# Schmatics_Hist_Prep.net
KiCad netlist of a schematic drawn in Altium Designer
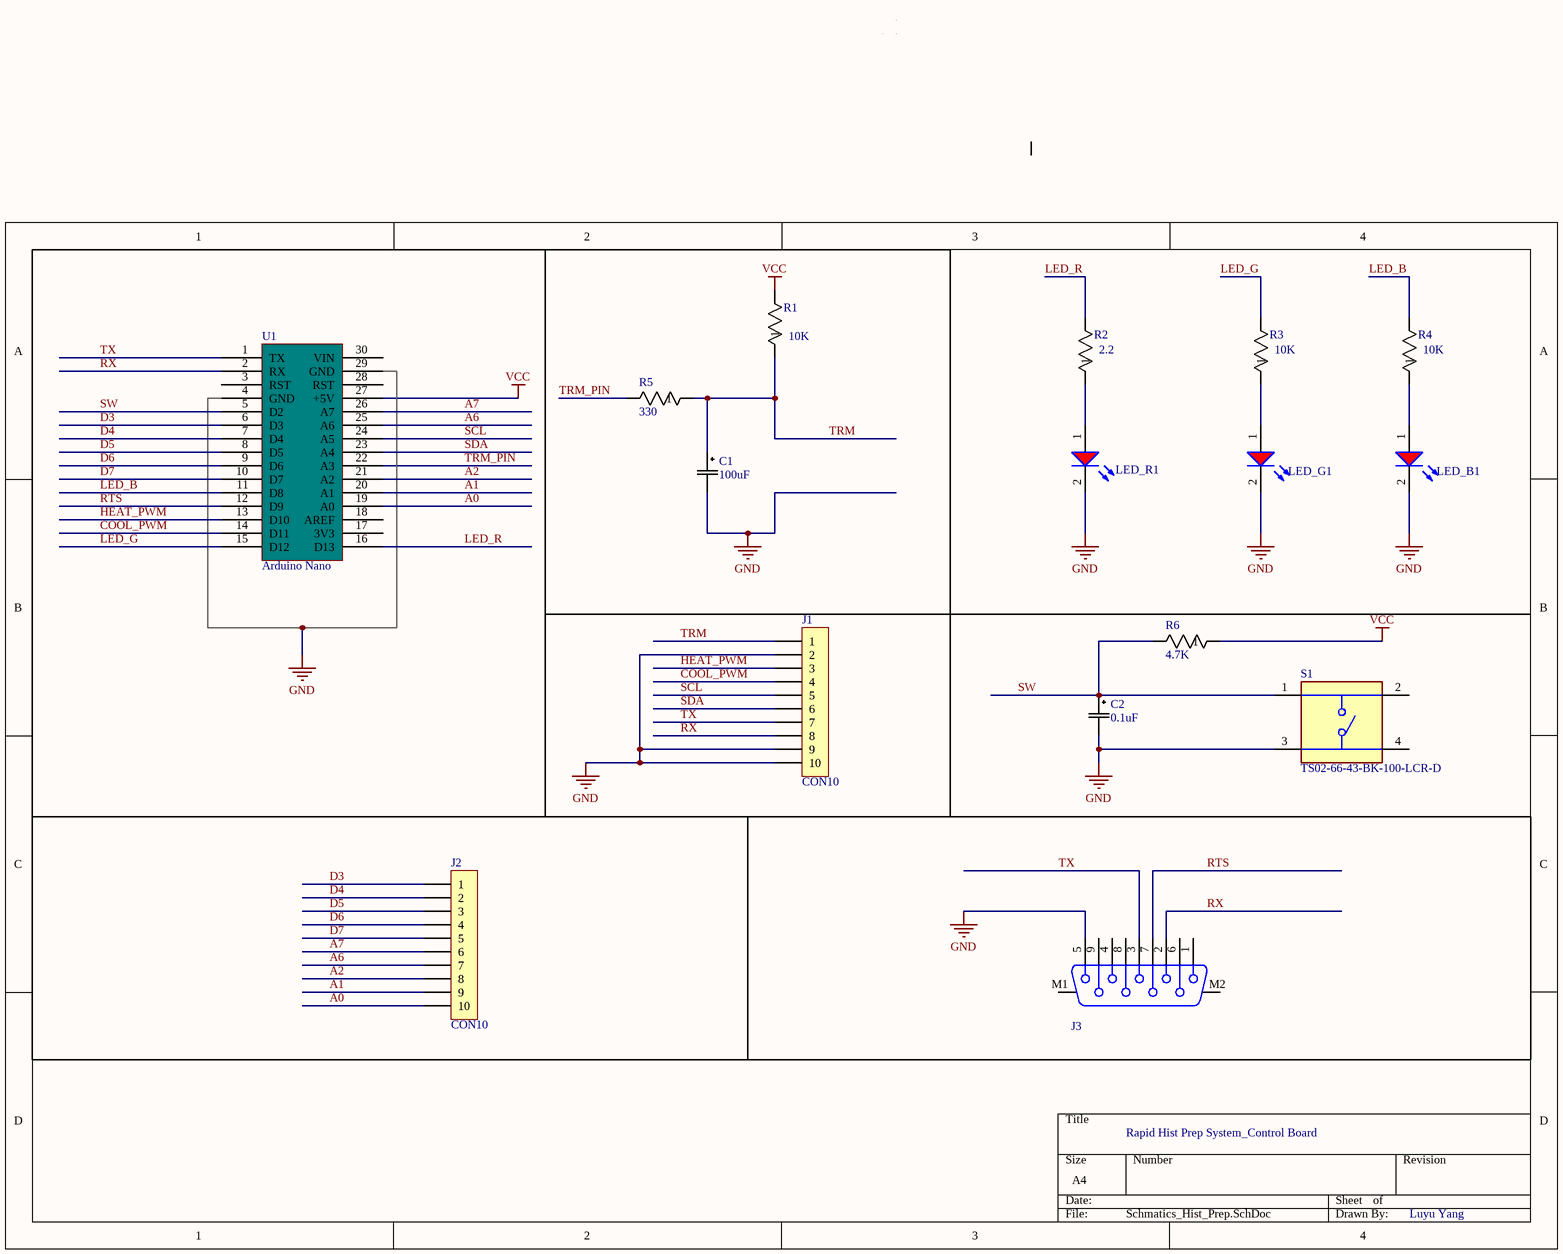
[diagram p0: Schmatics_Hist_Prep.SchDoc]

(export (version "E")
  (design (tool "Eeschema 10.0.6"))
  (components
    (comp (ref "C1")
      (value "100uF")
      (footprint "CAP_UKL_5X11_NCH")
      (description "No Description Available")
      (libsource (lib "UKL1H0R1MDDANATA") (part "UKL1H0R1MDDANATA"))
    )
    (comp (ref "C2")
      (value "0.1uF")
      (footprint "CAP_UKL_5X11_NCH")
      (description "No Description Available")
      (libsource (lib "UKL1H0R1MDDANATA") (part "UKL1H0R1MDDANATA"))
    )
    (comp (ref "J1") (value "CON10") (footprint "sip10") (libsource (lib "常用元件库") (part "CON10")))
    (comp (ref "J2") (value "CON10") (footprint "sip10") (libsource (lib "常用元件库") (part "CON10")))
    (comp (ref "J3")
      (value "61800925123")
      (footprint "61800925123")
      (description "WR-DSUB Female PCB Connector, Straight, 9p")
      (fields (field (name "MANUFACTURER") "Wurth Elektronik"))
      (libsource (lib "WR-DSUB") (part "61800925123"))
    )
    (comp (ref "LED_B1")
      (value "Super Red, 2V, 40°")
      (footprint "WL-TMRC_D3.95H5.3")
      (description "WL-TMRC Mono-color Round Color, THT, D3.95 x H5.3mm, Super Red, 2V, 40°")
      (fields
        (field (name "MANUFACTURER PART NUMBER") "151031SS04000")
        (field (name "MANUFACTURER") "Wurth Elektronik")
      )
      (libsource (lib "Altium_WL-TMRC_rev22b") (part "151031SS04000"))
    )
    (comp (ref "LED_G1")
      (value "Super Red, 2V, 40°")
      (footprint "WL-TMRC_D3.95H5.3")
      (description "WL-TMRC Mono-color Round Color, THT, D3.95 x H5.3mm, Super Red, 2V, 40°")
      (fields
        (field (name "MANUFACTURER PART NUMBER") "151031SS04000")
        (field (name "MANUFACTURER") "Wurth Elektronik")
      )
      (libsource (lib "Altium_WL-TMRC_rev22b") (part "151031SS04000"))
    )
    (comp (ref "LED_R1")
      (value "Super Red, 2V, 40°")
      (footprint "WL-TMRC_D3.95H5.3")
      (description "WL-TMRC Mono-color Round Color, THT, D3.95 x H5.3mm, Super Red, 2V, 40°")
      (fields
        (field (name "MANUFACTURER PART NUMBER") "151031SS04000")
        (field (name "MANUFACTURER") "Wurth Elektronik")
      )
      (libsource (lib "Altium_WL-TMRC_rev22b") (part "151031SS04000"))
    )
    (comp (ref "R1")
      (value "10K")
      (footprint "STA_CF14_STP")
      (description "No Description Available")
      (libsource (lib "CF14JT1K00") (part "CF14JT1K00"))
    )
    (comp (ref "R2")
      (value "2.2")
      (footprint "STA_CF14_STP")
      (description "No Description Available")
      (libsource (lib "CF14JT1K00") (part "CF14JT1K00"))
    )
    (comp (ref "R3")
      (value "10K")
      (footprint "STA_CF14_STP")
      (description "No Description Available")
      (libsource (lib "CF14JT1K00") (part "CF14JT1K00"))
    )
    (comp (ref "R4")
      (value "10K")
      (footprint "STA_CF14_STP")
      (description "No Description Available")
      (libsource (lib "CF14JT1K00") (part "CF14JT1K00"))
    )
    (comp (ref "R5")
      (value "330")
      (footprint "STA_CF14_STP")
      (description "No Description Available")
      (libsource (lib "CF14JT1K00") (part "CF14JT1K00"))
    )
    (comp (ref "R6")
      (value "4.7K")
      (footprint "STA_CF14_STP")
      (description "No Description Available")
      (libsource (lib "CF14JT1K00") (part "CF14JT1K00"))
    )
    (comp (ref "S1")
      (value "TS02-66-43-BK-100-LCR-D")
      (footprint "SW_TS02-66-43-BK-100-LCR-D")
      (description "6 x 6 mm, 4.3 mm Actuator Height, 100 gf, Black, Long Crimped, Through Hole, SPST, Tactile Switch")
      (fields (field (name "MF") "CUI Devices"))
      (libsource (lib "TS02-66-43-BK-100-LCR-D") (part "TS02-66-43-BK-100-LCR-D"))
    )
    (comp (ref "U1")
      (value "Arduino Nano")
      (footprint "PCBComponent_1")
      (libsource (lib "Nano") (part "Component_1"))
    )
  )
  (nets
    (net (code "1") (name "/A0") (class "Default")
      (node (ref "J2") (pin "10") (pinfunction "10_10") (pintype "passive"))
      (node (ref "U1") (pin "19") (pinfunction "A0_19") (pintype "passive"))
    )
    (net (code "2") (name "/A1") (class "Default")
      (node (ref "J2") (pin "9") (pinfunction "9_9") (pintype "passive"))
      (node (ref "U1") (pin "20") (pinfunction "A1_20") (pintype "passive"))
    )
    (net (code "3") (name "/A2") (class "Default")
      (node (ref "J2") (pin "8") (pinfunction "8_8") (pintype "passive"))
      (node (ref "U1") (pin "21") (pinfunction "A2_21") (pintype "passive"))
    )
    (net (code "4") (name "/A6") (class "Default")
      (node (ref "J2") (pin "7") (pinfunction "7_7") (pintype "passive"))
      (node (ref "U1") (pin "25") (pinfunction "A6_25") (pintype "passive"))
    )
    (net (code "5") (name "/A7") (class "Default")
      (node (ref "J2") (pin "6") (pinfunction "6_6") (pintype "passive"))
      (node (ref "U1") (pin "26") (pinfunction "A7_26") (pintype "passive"))
    )
    (net (code "6") (name "/COOL_PWM") (class "Default")
      (node (ref "J1") (pin "4") (pinfunction "4_4") (pintype "passive"))
      (node (ref "U1") (pin "14") (pinfunction "D11_14") (pintype "passive"))
    )
    (net (code "7") (name "/D3") (class "Default")
      (node (ref "J2") (pin "1") (pinfunction "1_1") (pintype "passive"))
      (node (ref "U1") (pin "6") (pinfunction "D3_6") (pintype "passive"))
    )
    (net (code "8") (name "/D4") (class "Default")
      (node (ref "J2") (pin "2") (pinfunction "2_2") (pintype "passive"))
      (node (ref "U1") (pin "7") (pinfunction "D4_7") (pintype "passive"))
    )
    (net (code "9") (name "/D5") (class "Default")
      (node (ref "J2") (pin "3") (pinfunction "3_3") (pintype "passive"))
      (node (ref "U1") (pin "8") (pinfunction "D5_8") (pintype "passive"))
    )
    (net (code "10") (name "/D6") (class "Default")
      (node (ref "J2") (pin "4") (pinfunction "4_4") (pintype "passive"))
      (node (ref "U1") (pin "9") (pinfunction "D6_9") (pintype "passive"))
    )
    (net (code "11") (name "/D7") (class "Default")
      (node (ref "J2") (pin "5") (pinfunction "5_5") (pintype "passive"))
      (node (ref "U1") (pin "10") (pinfunction "D7_10") (pintype "passive"))
    )
    (net (code "12") (name "/HEAT_PWM") (class "Default")
      (node (ref "J1") (pin "3") (pinfunction "3_3") (pintype "passive"))
      (node (ref "U1") (pin "13") (pinfunction "D10_13") (pintype "passive"))
    )
    (net (code "13") (name "/LED_B") (class "Default")
      (node (ref "R4") (pin "2") (pinfunction "2_2") (pintype "passive"))
      (node (ref "U1") (pin "11") (pinfunction "D8_11") (pintype "passive"))
    )
    (net (code "14") (name "/LED_G") (class "Default")
      (node (ref "R3") (pin "2") (pinfunction "2_2") (pintype "passive"))
      (node (ref "U1") (pin "15") (pinfunction "D12_15") (pintype "passive"))
    )
    (net (code "15") (name "/LED_R") (class "Default")
      (node (ref "R2") (pin "2") (pinfunction "2_2") (pintype "passive"))
      (node (ref "U1") (pin "16") (pinfunction "D13_16") (pintype "passive"))
    )
    (net (code "16") (name "/RTS") (class "Default")
      (node (ref "J3") (pin "7") (pinfunction "7_7") (pintype "passive"))
      (node (ref "U1") (pin "12") (pinfunction "D9_12") (pintype "passive"))
    )
    (net (code "17") (name "/RX") (class "Default")
      (node (ref "J1") (pin "8") (pinfunction "8_8") (pintype "passive"))
      (node (ref "J3") (pin "2") (pinfunction "2_2") (pintype "passive"))
      (node (ref "U1") (pin "2") (pinfunction "RX_2") (pintype "passive"))
    )
    (net (code "18") (name "/SCL") (class "Default")
      (node (ref "J1") (pin "5") (pinfunction "5_5") (pintype "passive"))
      (node (ref "U1") (pin "24") (pinfunction "A5_24") (pintype "passive"))
    )
    (net (code "19") (name "/SDA") (class "Default")
      (node (ref "J1") (pin "6") (pinfunction "6_6") (pintype "passive"))
      (node (ref "U1") (pin "23") (pinfunction "A4_23") (pintype "passive"))
    )
    (net (code "20") (name "/SW") (class "Default")
      (node (ref "C2") (pin "1") (pinfunction "1_1") (pintype "passive"))
      (node (ref "R6") (pin "2") (pinfunction "2_2") (pintype "passive"))
      (node (ref "S1") (pin "1") (pinfunction "1_1") (pintype "passive"))
      (node (ref "U1") (pin "5") (pinfunction "D2_5") (pintype "passive"))
    )
    (net (code "21") (name "/TRM") (class "Default")
      (node (ref "C1") (pin "1") (pinfunction "1_1") (pintype "passive"))
      (node (ref "J1") (pin "1") (pinfunction "1_1") (pintype "passive"))
      (node (ref "R1") (pin "1") (pinfunction "1_1") (pintype "passive"))
      (node (ref "R5") (pin "1") (pinfunction "1_1") (pintype "passive"))
    )
    (net (code "22") (name "/TRM_PIN") (class "Default")
      (node (ref "R5") (pin "2") (pinfunction "2_2") (pintype "passive"))
      (node (ref "U1") (pin "22") (pinfunction "A3_22") (pintype "passive"))
    )
    (net (code "23") (name "/TX") (class "Default")
      (node (ref "J1") (pin "7") (pinfunction "7_7") (pintype "passive"))
      (node (ref "J3") (pin "3") (pinfunction "3_3") (pintype "passive"))
      (node (ref "U1") (pin "1") (pinfunction "TX_1") (pintype "passive"))
    )
    (net (code "24") (name "GND") (class "Default")
      (node (ref "C1") (pin "2") (pinfunction "2_2") (pintype "passive"))
      (node (ref "C2") (pin "2") (pinfunction "2_2") (pintype "passive"))
      (node (ref "J1") (pin "10") (pinfunction "10_10") (pintype "passive"))
      (node (ref "J1") (pin "2") (pinfunction "2_2") (pintype "passive"))
      (node (ref "J1") (pin "9") (pinfunction "9_9") (pintype "passive"))
      (node (ref "J3") (pin "5") (pinfunction "5_5") (pintype "passive"))
      (node (ref "LED_B1") (pin "2") (pinfunction "K_2") (pintype "passive"))
      (node (ref "LED_G1") (pin "2") (pinfunction "K_2") (pintype "passive"))
      (node (ref "LED_R1") (pin "2") (pinfunction "K_2") (pintype "passive"))
      (node (ref "S1") (pin "3") (pinfunction "3_3") (pintype "passive"))
      (node (ref "U1") (pin "29") (pinfunction "GND_29") (pintype "passive"))
      (node (ref "U1") (pin "4") (pinfunction "GND_4") (pintype "passive"))
    )
    (net (code "25") (name "Net-(LED_B1-A)") (class "Default")
      (node (ref "LED_B1") (pin "1") (pinfunction "A_1") (pintype "passive"))
      (node (ref "R4") (pin "1") (pinfunction "1_1") (pintype "passive"))
    )
    (net (code "26") (name "Net-(LED_G1-A)") (class "Default")
      (node (ref "LED_G1") (pin "1") (pinfunction "A_1") (pintype "passive"))
      (node (ref "R3") (pin "1") (pinfunction "1_1") (pintype "passive"))
    )
    (net (code "27") (name "Net-(LED_R1-A)") (class "Default")
      (node (ref "LED_R1") (pin "1") (pinfunction "A_1") (pintype "passive"))
      (node (ref "R2") (pin "1") (pinfunction "1_1") (pintype "passive"))
    )
    (net (code "28") (name "VCC") (class "Default")
      (node (ref "R1") (pin "2") (pinfunction "2_2") (pintype "passive"))
      (node (ref "R6") (pin "1") (pinfunction "1_1") (pintype "passive"))
      (node (ref "U1") (pin "27") (pinfunction "+5V_27") (pintype "passive"))
    )
    (net (code "29") (name "unconnected-(J3-Pad1)") (class "Default")
      (node (ref "J3") (pin "1") (pinfunction "1_1") (pintype "passive"))
    )
    (net (code "30") (name "unconnected-(J3-Pad4)") (class "Default")
      (node (ref "J3") (pin "4") (pinfunction "4_4") (pintype "passive"))
    )
    (net (code "31") (name "unconnected-(J3-Pad6)") (class "Default")
      (node (ref "J3") (pin "6") (pinfunction "6_6") (pintype "passive"))
    )
    (net (code "32") (name "unconnected-(J3-Pad8)") (class "Default")
      (node (ref "J3") (pin "8") (pinfunction "8_8") (pintype "passive"))
    )
    (net (code "33") (name "unconnected-(J3-Pad9)") (class "Default")
      (node (ref "J3") (pin "9") (pinfunction "9_9") (pintype "passive"))
    )
    (net (code "34") (name "unconnected-(J3-PadM1)") (class "Default")
      (node (ref "J3") (pin "M1") (pinfunction "M1_M1") (pintype "passive"))
    )
    (net (code "35") (name "unconnected-(J3-PadM2)") (class "Default")
      (node (ref "J3") (pin "M2") (pinfunction "M2_M2") (pintype "passive"))
    )
    (net (code "36") (name "unconnected-(S1-Pad2)") (class "Default")
      (node (ref "S1") (pin "2") (pinfunction "2_2") (pintype "passive"))
    )
    (net (code "37") (name "unconnected-(S1-Pad4)") (class "Default")
      (node (ref "S1") (pin "4") (pinfunction "4_4") (pintype "passive"))
    )
    (net (code "38") (name "unconnected-(U1-3V3-Pad17)") (class "Default")
      (node (ref "U1") (pin "17") (pinfunction "3V3_17") (pintype "passive"))
    )
    (net (code "39") (name "unconnected-(U1-AREF-Pad18)") (class "Default")
      (node (ref "U1") (pin "18") (pinfunction "AREF_18") (pintype "passive"))
    )
    (net (code "40") (name "unconnected-(U1-RST-Pad3)") (class "Default")
      (node (ref "U1") (pin "3") (pinfunction "RST_3") (pintype "passive"))
    )
    (net (code "41") (name "unconnected-(U1-RST-Pad28)") (class "Default")
      (node (ref "U1") (pin "28") (pinfunction "RST_28") (pintype "passive"))
    )
    (net (code "42") (name "unconnected-(U1-VIN-Pad30)") (class "Default")
      (node (ref "U1") (pin "30") (pinfunction "VIN_30") (pintype "passive"))
    )
  )
)
